# Relay.net
KiCad netlist of a schematic drawn in Altium Designer
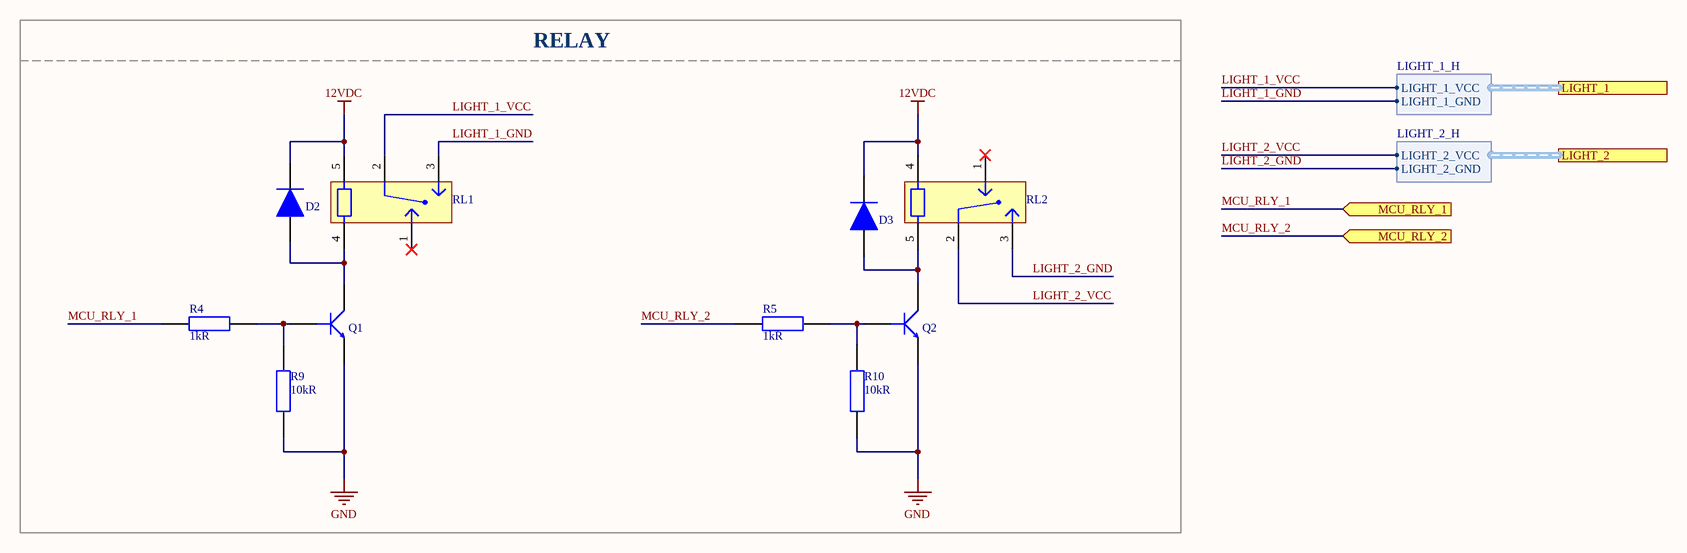
[diagram p0: Relay.SchDoc]

(export (version "E")
  (design (tool "Eeschema 10.0.6"))
  (components
    (comp (ref "D2")
      (value "1N4148WS")
      (footprint "SOD323F")
      (description "Diode, Single, 75 V, 150 mA, 1 V, 4 ns")
      (fields
        (field (name "MANUFACTURER") "ON Semiconductor / Fairchild")
        (field (name "DESIGNED BY") "BERK")
      )
      (libsource (lib "GuvenlikSistemi_Library") (part "1N4148WS"))
    )
    (comp (ref "D3")
      (value "1N4148WS")
      (footprint "SOD323F")
      (description "Diode, Single, 75 V, 150 mA, 1 V, 4 ns")
      (fields
        (field (name "MANUFACTURER") "ON Semiconductor / Fairchild")
        (field (name "DESIGNED BY") "BERK")
      )
      (libsource (lib "GuvenlikSistemi_Library") (part "1N4148WS"))
    )
    (comp (ref "Q1")
      (value "MMBT3904-7-F")
      (footprint "SOT-23F")
      (description "Transistor General Purpose BJT NPN 40 Volt 0.2A Automotive 3-Pin SOT-23")
      (fields (field (name "MANUFACTURER") "Diodes Zetex") (field (name "DESIGNED BY") "BERK"))
      (libsource (lib "GuvenlikSistemi_Library") (part "MMBT3904-7-F"))
    )
    (comp (ref "Q2")
      (value "MMBT3904-7-F")
      (footprint "SOT-23F")
      (description "Transistor General Purpose BJT NPN 40 Volt 0.2A Automotive 3-Pin SOT-23")
      (fields (field (name "MANUFACTURER") "Diodes Zetex") (field (name "DESIGNED BY") "BERK"))
      (libsource (lib "GuvenlikSistemi_Library") (part "MMBT3904-7-F"))
    )
    (comp (ref "R4")
      (value "RC0603FR-0710KL")
      (footprint "RES_0603")
      (description "RES 1K %1 OHM 0603 SMD")
      (fields
        (field (name "MANUFACTURER") "Yageo")
        (field (name "MANUFACTURER PART NUMBER") "RC0603JR-071KL")
        (field (name "RESISTANCE") "1kR")
        (field (name "DESIGNED BY") "BERK")
      )
      (libsource (lib "GuvenlikSistemi_Library") (part "RES 1K OHM 0603"))
    )
    (comp (ref "R5")
      (value "RC0603FR-0710KL")
      (footprint "RES_0603")
      (description "RES 1K %1 OHM 0603 SMD")
      (fields
        (field (name "MANUFACTURER") "Yageo")
        (field (name "MANUFACTURER PART NUMBER") "RC0603JR-071KL")
        (field (name "RESISTANCE") "1kR")
        (field (name "DESIGNED BY") "BERK")
      )
      (libsource (lib "GuvenlikSistemi_Library") (part "RES 1K OHM 0603"))
    )
    (comp (ref "R9")
      (value "RC0603FR-0710KL")
      (footprint "RES_0603")
      (description "RES 10K %1 OHM 0603 SMD")
      (fields
        (field (name "MANUFACTURER") "Yageo")
        (field (name "TOLERANCE") "1%")
        (field (name "RESISTANCE") "10kR")
        (field (name "DESIGNED BY") "BERK")
      )
      (libsource (lib "GuvenlikSistemi_Library") (part "RES 10K OHM 0603"))
    )
    (comp (ref "R10")
      (value "RC0603FR-0710KL")
      (footprint "RES_0603")
      (description "RES 10K %1 OHM 0603 SMD")
      (fields
        (field (name "MANUFACTURER") "Yageo")
        (field (name "TOLERANCE") "1%")
        (field (name "RESISTANCE") "10kR")
        (field (name "DESIGNED BY") "BERK")
      )
      (libsource (lib "GuvenlikSistemi_Library") (part "RES 10K OHM 0603"))
    )
    (comp (ref "RL1")
      (value "ALQ112")
      (footprint "ALQ112")
      (description "General Purpose Relay SPDT (1 Form C) 12VDC Coil Through Hole")
      (fields (field (name "MANUFACTURER") "Panasonic") (field (name "DESIGNED BY") "BERK"))
      (libsource (lib "") (part "ALQ112_1"))
    )
    (comp (ref "RL2")
      (value "ALQ112")
      (footprint "ALQ112")
      (description "General Purpose Relay SPDT (1 Form C) 12VDC Coil Through Hole")
      (fields (field (name "MANUFACTURER") "Panasonic") (field (name "DESIGNED BY") "BERK"))
      (libsource (lib "GuvenlikSistemi_Library") (part "ALQ112"))
    )
  )
  (nets
    (net (code "3") (name "/LIGHT_1_GND") (class "Default")
      (node (ref "RL1") (pin "3") (pinfunction "3_3") (pintype "passive"))
    )
    (net (code "4") (name "/LIGHT_1_VCC") (class "Default")
      (node (ref "RL1") (pin "2") (pinfunction "2_2") (pintype "passive"))
    )
    (net (code "5") (name "/LIGHT_2_GND") (class "Default")
      (node (ref "RL2") (pin "3") (pinfunction "3_3") (pintype "passive"))
    )
    (net (code "6") (name "/LIGHT_2_VCC") (class "Default")
      (node (ref "RL2") (pin "2") (pinfunction "2_2") (pintype "passive"))
    )
    (net (code "7") (name "/MCU_RLY_1") (class "Default")
      (node (ref "R4") (pin "1") (pinfunction "1_1") (pintype "passive"))
    )
    (net (code "8") (name "/MCU_RLY_2") (class "Default")
      (node (ref "R5") (pin "1") (pinfunction "1_1") (pintype "passive"))
    )
    (net (code "11") (name "12VDC") (class "Default")
      (node (ref "D2") (pin "1") (pinfunction "1_1") (pintype "power_in"))
      (node (ref "D3") (pin "1") (pinfunction "1_1") (pintype "power_in"))
      (node (ref "RL1") (pin "5") (pinfunction "5_5") (pintype "passive"))
      (node (ref "RL2") (pin "4") (pinfunction "4_4") (pintype "passive"))
    )
    (net (code "12") (name "GND") (class "Default")
      (node (ref "Q1") (pin "2") (pinfunction "E_2") (pintype "power_in"))
      (node (ref "Q2") (pin "2") (pinfunction "E_2") (pintype "power_in"))
      (node (ref "R10") (pin "1") (pinfunction "1_1") (pintype "passive"))
      (node (ref "R9") (pin "1") (pinfunction "1_1") (pintype "passive"))
    )
    (net (code "13") (name "Net-(Q1-B)") (class "Default")
      (node (ref "Q1") (pin "1") (pinfunction "B_1") (pintype "power_in"))
      (node (ref "R4") (pin "2") (pinfunction "2_2") (pintype "passive"))
      (node (ref "R9") (pin "2") (pinfunction "2_2") (pintype "passive"))
    )
    (net (code "14") (name "Net-(Q1-C)") (class "Default")
      (node (ref "D2") (pin "2") (pinfunction "2_2") (pintype "power_in"))
      (node (ref "Q1") (pin "3") (pinfunction "C_3") (pintype "power_in"))
      (node (ref "RL1") (pin "4") (pinfunction "4_4") (pintype "passive"))
    )
    (net (code "15") (name "Net-(Q2-B)") (class "Default")
      (node (ref "Q2") (pin "1") (pinfunction "B_1") (pintype "power_in"))
      (node (ref "R10") (pin "2") (pinfunction "2_2") (pintype "passive"))
      (node (ref "R5") (pin "2") (pinfunction "2_2") (pintype "passive"))
    )
    (net (code "16") (name "Net-(Q2-C)") (class "Default")
      (node (ref "D3") (pin "2") (pinfunction "2_2") (pintype "power_in"))
      (node (ref "Q2") (pin "3") (pinfunction "C_3") (pintype "power_in"))
      (node (ref "RL2") (pin "5") (pinfunction "5_5") (pintype "passive"))
    )
    (net (code "17") (name "unconnected-(RL1-Pad1)") (class "Default")
      (node (ref "RL1") (pin "1") (pinfunction "1_1") (pintype "passive+no_connect"))
    )
    (net (code "18") (name "unconnected-(RL2-Pad1)") (class "Default")
      (node (ref "RL2") (pin "1") (pinfunction "1_1") (pintype "passive+no_connect"))
    )
  )
)
